# ESPLed.net
KiCad netlist of a schematic drawn in EAGLE
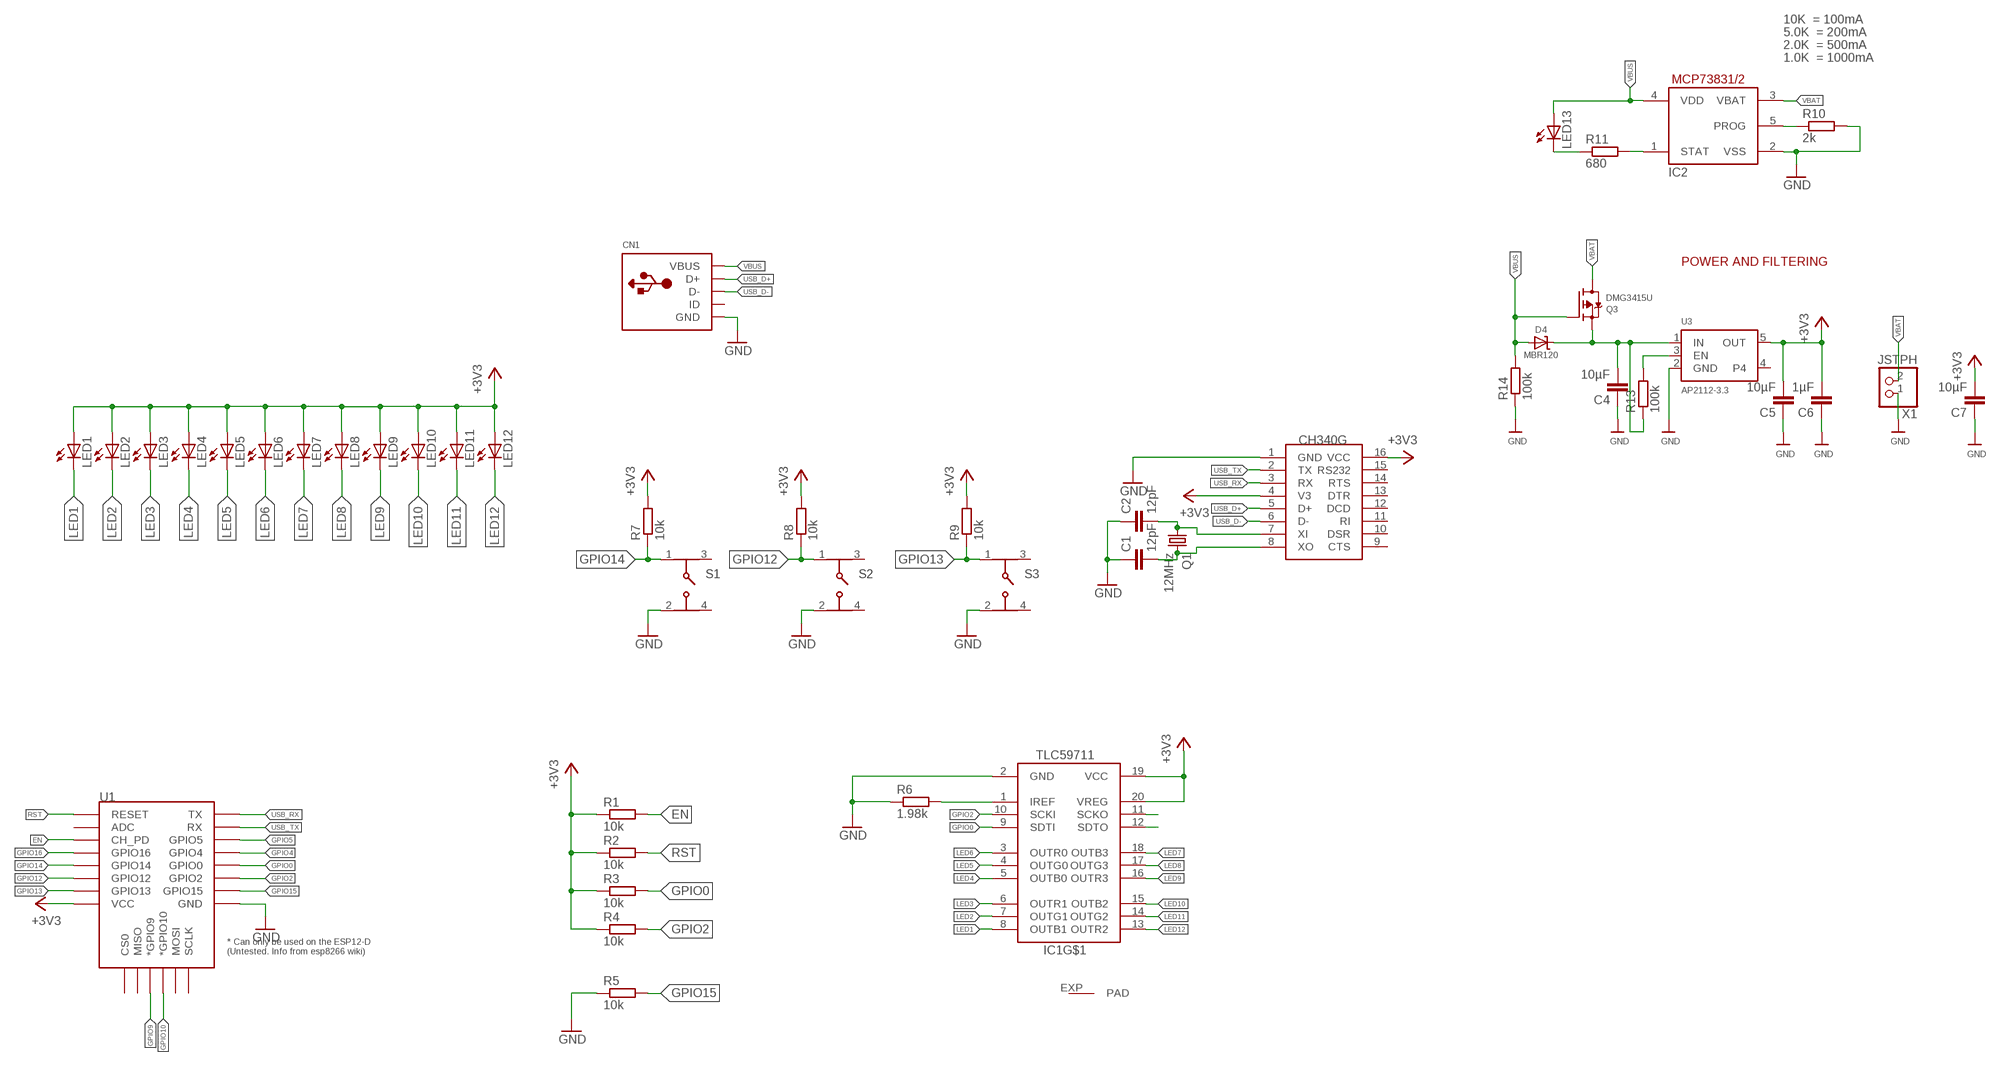
[diagram p0: schematic, sheet 1]

(export (version "E")
  (design (tool "Eeschema 10.0.6"))
  (components
    (comp (ref "C1")
      (value "12pF")
      (footprint "eagle-import:C0805")
      (libsource (lib "eagle-import") (part "C-EUC0805"))
    )
    (comp (ref "C2")
      (value "12pF")
      (footprint "eagle-import:C0805")
      (libsource (lib "eagle-import") (part "C-EUC0805"))
    )
    (comp (ref "C4")
      (value "10µF")
      (footprint "eagle-import:C0805")
      (libsource (lib "eagle-import") (part "C-EUC0805"))
    )
    (comp (ref "C5")
      (value "10µF")
      (footprint "eagle-import:C0805")
      (libsource (lib "eagle-import") (part "C-EUC0805"))
    )
    (comp (ref "C6")
      (value "1µF")
      (footprint "eagle-import:C0805")
      (libsource (lib "eagle-import") (part "C-EUC0805"))
    )
    (comp (ref "C7")
      (value "10µF")
      (footprint "eagle-import:C0805")
      (libsource (lib "eagle-import") (part "C-EUC0805"))
    )
    (comp (ref "CN1")
      (value "USBMINIB")
      (footprint "eagle-import:USB-MINIB")
      (libsource (lib "eagle-import") (part "USBMINIB"))
    )
    (comp (ref "D4")
      (value "MBR120")
      (footprint "eagle-import:SOD-123")
      (libsource (lib "eagle-import") (part "DIODE-SCHOTTKYSOD-123"))
    )
    (comp (ref "IC1")
      (value "TLC59711")
      (footprint "eagle-import:HTSSOP20DAP")
      (libsource (lib "eagle-import") (part "TLC59711"))
    )
    (comp (ref "IC2")
      (value "MCP73831/OT")
      (footprint "eagle-import:SOT23-5L")
      (libsource (lib "eagle-import") (part "MCP73831/OT"))
    )
    (comp (ref "LED1")
      (value "LEDSML0805")
      (footprint "eagle-import:SML0805")
      (libsource (lib "eagle-import") (part "LEDSML0805"))
    )
    (comp (ref "LED2")
      (value "LEDSML0805")
      (footprint "eagle-import:SML0805")
      (libsource (lib "eagle-import") (part "LEDSML0805"))
    )
    (comp (ref "LED3")
      (value "LEDSML0805")
      (footprint "eagle-import:SML0805")
      (libsource (lib "eagle-import") (part "LEDSML0805"))
    )
    (comp (ref "LED4")
      (value "LEDSML0805")
      (footprint "eagle-import:SML0805")
      (libsource (lib "eagle-import") (part "LEDSML0805"))
    )
    (comp (ref "LED5")
      (value "LEDSML0805")
      (footprint "eagle-import:SML0805")
      (libsource (lib "eagle-import") (part "LEDSML0805"))
    )
    (comp (ref "LED6")
      (value "LEDSML0805")
      (footprint "eagle-import:SML0805")
      (libsource (lib "eagle-import") (part "LEDSML0805"))
    )
    (comp (ref "LED7")
      (value "LEDSML0805")
      (footprint "eagle-import:SML0805")
      (libsource (lib "eagle-import") (part "LEDSML0805"))
    )
    (comp (ref "LED8")
      (value "LEDSML0805")
      (footprint "eagle-import:SML0805")
      (libsource (lib "eagle-import") (part "LEDSML0805"))
    )
    (comp (ref "LED9")
      (value "LEDSML0805")
      (footprint "eagle-import:SML0805")
      (libsource (lib "eagle-import") (part "LEDSML0805"))
    )
    (comp (ref "LED10")
      (value "LEDSML0805")
      (footprint "eagle-import:SML0805")
      (libsource (lib "eagle-import") (part "LEDSML0805"))
    )
    (comp (ref "LED11")
      (value "LEDSML0805")
      (footprint "eagle-import:SML0805")
      (libsource (lib "eagle-import") (part "LEDSML0805"))
    )
    (comp (ref "LED12")
      (value "LEDSML0805")
      (footprint "eagle-import:SML0805")
      (libsource (lib "eagle-import") (part "LEDSML0805"))
    )
    (comp (ref "LED13")
      (value "LEDSML0805")
      (footprint "eagle-import:SML0805")
      (libsource (lib "eagle-import") (part "LEDSML0805"))
    )
    (comp (ref "Q1")
      (value "12MHz")
      (footprint "eagle-import:CX5032GB")
      (libsource (lib "eagle-import") (part "CX5032GB12000H0PESZZ"))
    )
    (comp (ref "Q3")
      (value "DMG3415U")
      (footprint "eagle-import:SOT23-R")
      (libsource (lib "eagle-import") (part "MOSFET-P"))
    )
    (comp (ref "R1")
      (value "10k")
      (footprint "eagle-import:R0805")
      (libsource (lib "eagle-import") (part "R-EU_R0805"))
    )
    (comp (ref "R2")
      (value "10k")
      (footprint "eagle-import:R0805")
      (libsource (lib "eagle-import") (part "R-EU_R0805"))
    )
    (comp (ref "R3")
      (value "10k")
      (footprint "eagle-import:R0805")
      (libsource (lib "eagle-import") (part "R-EU_R0805"))
    )
    (comp (ref "R4")
      (value "10k")
      (footprint "eagle-import:R0805")
      (libsource (lib "eagle-import") (part "R-EU_R0805"))
    )
    (comp (ref "R5")
      (value "10k")
      (footprint "eagle-import:R0805")
      (libsource (lib "eagle-import") (part "R-EU_R0805"))
    )
    (comp (ref "R6")
      (value "1.98k")
      (footprint "eagle-import:R0805")
      (libsource (lib "eagle-import") (part "R-EU_R0805"))
    )
    (comp (ref "R7")
      (value "10k")
      (footprint "eagle-import:R0805")
      (libsource (lib "eagle-import") (part "R-EU_R0805"))
    )
    (comp (ref "R8")
      (value "10k")
      (footprint "eagle-import:R0805")
      (libsource (lib "eagle-import") (part "R-EU_R0805"))
    )
    (comp (ref "R9")
      (value "10k")
      (footprint "eagle-import:R0805")
      (libsource (lib "eagle-import") (part "R-EU_R0805"))
    )
    (comp (ref "R10")
      (value "2k")
      (footprint "eagle-import:R0805")
      (libsource (lib "eagle-import") (part "R-EU_R0805"))
    )
    (comp (ref "R11")
      (value "680")
      (footprint "eagle-import:R0805")
      (libsource (lib "eagle-import") (part "R-EU_R0805"))
    )
    (comp (ref "R13")
      (value "100k")
      (footprint "eagle-import:R0805")
      (libsource (lib "eagle-import") (part "R-EU_R0805"))
    )
    (comp (ref "R14")
      (value "100k")
      (footprint "eagle-import:R0805")
      (libsource (lib "eagle-import") (part "R-EU_R0805"))
    )
    (comp (ref "S1")
      (value "4301X6XXX7X6_430156043726")
      (footprint "eagle-import:4301X6XXX7X6")
      (libsource (lib "eagle-import") (part "4301X6XXX7X6_430156043726"))
    )
    (comp (ref "S2")
      (value "4301X6XXX7X6_430156043726")
      (footprint "eagle-import:4301X6XXX7X6")
      (libsource (lib "eagle-import") (part "4301X6XXX7X6_430156043726"))
    )
    (comp (ref "S3")
      (value "4301X6XXX7X6_430156043726")
      (footprint "eagle-import:4301X6XXX7X6")
      (libsource (lib "eagle-import") (part "4301X6XXX7X6_430156043726"))
    )
    (comp (ref "U$1")
      (value "CH340G")
      (footprint "eagle-import:SOIC16")
      (libsource (lib "eagle-import") (part "CH340G"))
    )
    (comp (ref "U1")
      (value "ESP12ESMD")
      (footprint "eagle-import:ESP12E-SMD")
      (libsource (lib "eagle-import") (part "ESP12ESMD"))
    )
    (comp (ref "U3")
      (value "AP2112-3.3")
      (footprint "eagle-import:SOT23-5")
      (libsource (lib "eagle-import") (part "VREG_SOT23-5"))
    )
    (comp (ref "X1")
      (value "JSTPH")
      (footprint "eagle-import:JSTPH2")
      (libsource (lib "eagle-import") (part "CON_JST_PH_2PIN"))
    )
  )
  (nets
    (net (code "1") (name "+3V3") (class "Default")
      (node (ref "C5") (pin "2") (pinfunction "2_2") (pintype "passive"))
      (node (ref "C6") (pin "2") (pinfunction "2_2") (pintype "passive"))
      (node (ref "C7") (pin "2") (pinfunction "2_2") (pintype "passive"))
      (node (ref "IC1") (pin "19") (pinfunction "VCC_19") (pintype "power_in"))
      (node (ref "IC1") (pin "20") (pinfunction "VREG_20") (pintype "bidirectional"))
      (node (ref "LED1") (pin "A") (pinfunction "A_A") (pintype "passive"))
      (node (ref "LED10") (pin "A") (pinfunction "A_A") (pintype "passive"))
      (node (ref "LED11") (pin "A") (pinfunction "A_A") (pintype "passive"))
      (node (ref "LED12") (pin "A") (pinfunction "A_A") (pintype "passive"))
      (node (ref "LED2") (pin "A") (pinfunction "A_A") (pintype "passive"))
      (node (ref "LED3") (pin "A") (pinfunction "A_A") (pintype "passive"))
      (node (ref "LED4") (pin "A") (pinfunction "A_A") (pintype "passive"))
      (node (ref "LED5") (pin "A") (pinfunction "A_A") (pintype "passive"))
      (node (ref "LED6") (pin "A") (pinfunction "A_A") (pintype "passive"))
      (node (ref "LED7") (pin "A") (pinfunction "A_A") (pintype "passive"))
      (node (ref "LED8") (pin "A") (pinfunction "A_A") (pintype "passive"))
      (node (ref "LED9") (pin "A") (pinfunction "A_A") (pintype "passive"))
      (node (ref "R1") (pin "1") (pinfunction "1_1") (pintype "passive"))
      (node (ref "R2") (pin "1") (pinfunction "1_1") (pintype "passive"))
      (node (ref "R3") (pin "1") (pinfunction "1_1") (pintype "passive"))
      (node (ref "R4") (pin "1") (pinfunction "1_1") (pintype "passive"))
      (node (ref "R7") (pin "2") (pinfunction "2_2") (pintype "passive"))
      (node (ref "R8") (pin "2") (pinfunction "2_2") (pintype "passive"))
      (node (ref "R9") (pin "2") (pinfunction "2_2") (pintype "passive"))
      (node (ref "U$1") (pin "16") (pinfunction "VCC_16") (pintype "bidirectional"))
      (node (ref "U$1") (pin "4") (pinfunction "V3_4") (pintype "bidirectional"))
      (node (ref "U1") (pin "VCC") (pinfunction "VCC_VCC") (pintype "bidirectional"))
      (node (ref "U3") (pin "5") (pinfunction "OUT_5") (pintype "power_in"))
    )
    (net (code "2") (name "EN") (class "Default")
      (node (ref "R1") (pin "2") (pinfunction "2_2") (pintype "passive"))
      (node (ref "U1") (pin "CH_PD") (pinfunction "CH_PD_CH_PD") (pintype "bidirectional"))
    )
    (net (code "3") (name "GND") (class "Default")
      (node (ref "C1") (pin "1") (pinfunction "1_1") (pintype "passive"))
      (node (ref "C2") (pin "1") (pinfunction "1_1") (pintype "passive"))
      (node (ref "C4") (pin "1") (pinfunction "1_1") (pintype "passive"))
      (node (ref "C5") (pin "1") (pinfunction "1_1") (pintype "passive"))
      (node (ref "C6") (pin "1") (pinfunction "1_1") (pintype "passive"))
      (node (ref "C7") (pin "1") (pinfunction "1_1") (pintype "passive"))
      (node (ref "CN1") (pin "GND") (pinfunction "GND_GND") (pintype "power_in"))
      (node (ref "IC1") (pin "2") (pinfunction "GND_2") (pintype "power_in"))
      (node (ref "IC2") (pin "2") (pinfunction "VSS_2") (pintype "power_in"))
      (node (ref "R10") (pin "2") (pinfunction "2_2") (pintype "passive"))
      (node (ref "R14") (pin "1") (pinfunction "1_1") (pintype "passive"))
      (node (ref "R5") (pin "1") (pinfunction "1_1") (pintype "passive"))
      (node (ref "R6") (pin "1") (pinfunction "1_1") (pintype "passive"))
      (node (ref "S1") (pin "2") (pinfunction "2_2") (pintype "passive"))
      (node (ref "S2") (pin "2") (pinfunction "2_2") (pintype "passive"))
      (node (ref "S3") (pin "2") (pinfunction "2_2") (pintype "passive"))
      (node (ref "U$1") (pin "1") (pinfunction "GND_1") (pintype "bidirectional"))
      (node (ref "U1") (pin "GND") (pinfunction "GND_GND") (pintype "bidirectional"))
      (node (ref "U3") (pin "2") (pinfunction "GND_2") (pintype "power_in"))
      (node (ref "X1") (pin "1") (pinfunction "1_1") (pintype "passive"))
    )
    (net (code "4") (name "GPIO0") (class "Default")
      (node (ref "IC1") (pin "9") (pinfunction "SDTI_9") (pintype "input"))
      (node (ref "R3") (pin "2") (pinfunction "2_2") (pintype "passive"))
      (node (ref "U1") (pin "GPIO0") (pinfunction "GPIO0_GPIO0") (pintype "bidirectional"))
    )
    (net (code "5") (name "GPIO2") (class "Default")
      (node (ref "IC1") (pin "10") (pinfunction "SCKI_10") (pintype "input"))
      (node (ref "R4") (pin "2") (pinfunction "2_2") (pintype "passive"))
      (node (ref "U1") (pin "GPIO2") (pinfunction "GPIO2_GPIO2") (pintype "bidirectional"))
    )
    (net (code "6") (name "GPIO4") (class "Default")
      (node (ref "U1") (pin "GPIO4") (pinfunction "GPIO4_GPIO4") (pintype "bidirectional"))
    )
    (net (code "7") (name "GPIO5") (class "Default")
      (node (ref "U1") (pin "GPIO5") (pinfunction "GPIO5_GPIO5") (pintype "bidirectional"))
    )
    (net (code "8") (name "GPIO9") (class "Default")
      (node (ref "U1") (pin "GPIO9") (pinfunction "*GPIO9_GPIO9") (pintype "bidirectional"))
    )
    (net (code "9") (name "GPIO10") (class "Default")
      (node (ref "U1") (pin "GPIO10") (pinfunction "*GPIO10_GPIO10") (pintype "bidirectional"))
    )
    (net (code "10") (name "GPIO12") (class "Default")
      (node (ref "R8") (pin "1") (pinfunction "1_1") (pintype "passive"))
      (node (ref "S2") (pin "1") (pinfunction "1_1") (pintype "passive"))
      (node (ref "U1") (pin "GPIO12") (pinfunction "GPIO12_GPIO12") (pintype "bidirectional"))
    )
    (net (code "11") (name "GPIO13") (class "Default")
      (node (ref "R9") (pin "1") (pinfunction "1_1") (pintype "passive"))
      (node (ref "S3") (pin "1") (pinfunction "1_1") (pintype "passive"))
      (node (ref "U1") (pin "GPIO13") (pinfunction "GPIO13_GPIO13") (pintype "bidirectional"))
    )
    (net (code "12") (name "GPIO14") (class "Default")
      (node (ref "R7") (pin "1") (pinfunction "1_1") (pintype "passive"))
      (node (ref "S1") (pin "1") (pinfunction "1_1") (pintype "passive"))
      (node (ref "U1") (pin "GPIO14") (pinfunction "GPIO14_GPIO14") (pintype "bidirectional"))
    )
    (net (code "13") (name "GPIO15") (class "Default")
      (node (ref "R5") (pin "2") (pinfunction "2_2") (pintype "passive"))
      (node (ref "U1") (pin "GPIO15") (pinfunction "GPIO15_GPIO15") (pintype "bidirectional"))
    )
    (net (code "14") (name "GPIO16") (class "Default")
      (node (ref "U1") (pin "GPIO16") (pinfunction "GPIO16_GPIO16") (pintype "bidirectional"))
    )
    (net (code "15") (name "LED1") (class "Default")
      (node (ref "IC1") (pin "8") (pinfunction "OUTB1_8") (pintype "open_collector"))
      (node (ref "LED1") (pin "C") (pinfunction "C_C") (pintype "passive"))
    )
    (net (code "16") (name "LED2") (class "Default")
      (node (ref "IC1") (pin "7") (pinfunction "OUTG1_7") (pintype "open_collector"))
      (node (ref "LED2") (pin "C") (pinfunction "C_C") (pintype "passive"))
    )
    (net (code "17") (name "LED3") (class "Default")
      (node (ref "IC1") (pin "6") (pinfunction "OUTR1_6") (pintype "open_collector"))
      (node (ref "LED3") (pin "C") (pinfunction "C_C") (pintype "passive"))
    )
    (net (code "18") (name "LED4") (class "Default")
      (node (ref "IC1") (pin "5") (pinfunction "OUTB0_5") (pintype "open_collector"))
      (node (ref "LED4") (pin "C") (pinfunction "C_C") (pintype "passive"))
    )
    (net (code "19") (name "LED5") (class "Default")
      (node (ref "IC1") (pin "4") (pinfunction "OUTG0_4") (pintype "open_collector"))
      (node (ref "LED5") (pin "C") (pinfunction "C_C") (pintype "passive"))
    )
    (net (code "20") (name "LED6") (class "Default")
      (node (ref "IC1") (pin "3") (pinfunction "OUTR0_3") (pintype "open_collector"))
      (node (ref "LED6") (pin "C") (pinfunction "C_C") (pintype "passive"))
    )
    (net (code "21") (name "LED7") (class "Default")
      (node (ref "IC1") (pin "18") (pinfunction "OUTB3_18") (pintype "open_collector"))
      (node (ref "LED7") (pin "C") (pinfunction "C_C") (pintype "passive"))
    )
    (net (code "22") (name "LED8") (class "Default")
      (node (ref "IC1") (pin "17") (pinfunction "OUTG3_17") (pintype "open_collector"))
      (node (ref "LED8") (pin "C") (pinfunction "C_C") (pintype "passive"))
    )
    (net (code "23") (name "LED9") (class "Default")
      (node (ref "IC1") (pin "16") (pinfunction "OUTR3_16") (pintype "open_collector"))
      (node (ref "LED9") (pin "C") (pinfunction "C_C") (pintype "passive"))
    )
    (net (code "24") (name "LED10") (class "Default")
      (node (ref "IC1") (pin "15") (pinfunction "OUTB2_15") (pintype "open_collector"))
      (node (ref "LED10") (pin "C") (pinfunction "C_C") (pintype "passive"))
    )
    (net (code "25") (name "LED11") (class "Default")
      (node (ref "IC1") (pin "14") (pinfunction "OUTG2_14") (pintype "open_collector"))
      (node (ref "LED11") (pin "C") (pinfunction "C_C") (pintype "passive"))
    )
    (net (code "26") (name "LED12") (class "Default")
      (node (ref "IC1") (pin "13") (pinfunction "OUTR2_13") (pintype "open_collector"))
      (node (ref "LED12") (pin "C") (pinfunction "C_C") (pintype "passive"))
    )
    (net (code "27") (name "Net-(IC1A-IREF)") (class "Default")
      (node (ref "IC1") (pin "1") (pinfunction "IREF_1") (pintype "bidirectional"))
      (node (ref "R6") (pin "2") (pinfunction "2_2") (pintype "passive"))
    )
    (net (code "28") (name "Net-(IC2-PROG)") (class "Default")
      (node (ref "IC2") (pin "5") (pinfunction "PROG_5") (pintype "input"))
      (node (ref "R10") (pin "1") (pinfunction "1_1") (pintype "passive"))
    )
    (net (code "29") (name "Net-(IC2-STAT)") (class "Default")
      (node (ref "IC2") (pin "1") (pinfunction "STAT_1") (pintype "output"))
      (node (ref "R11") (pin "2") (pinfunction "2_2") (pintype "passive"))
    )
    (net (code "30") (name "Net-(LED13-PadC)") (class "Default")
      (node (ref "LED13") (pin "C") (pinfunction "C_C") (pintype "passive"))
      (node (ref "R11") (pin "1") (pinfunction "1_1") (pintype "passive"))
    )
    (net (code "31") (name "Net-(Q1-1)") (class "Default")
      (node (ref "C2") (pin "2") (pinfunction "2_2") (pintype "passive"))
      (node (ref "Q1") (pin "P$1") (pinfunction "1_P$1") (pintype "passive"))
      (node (ref "U$1") (pin "7") (pinfunction "XI_7") (pintype "bidirectional"))
    )
    (net (code "32") (name "Net-(Q1-2)") (class "Default")
      (node (ref "C1") (pin "2") (pinfunction "2_2") (pintype "passive"))
      (node (ref "Q1") (pin "P$2") (pinfunction "2_P$2") (pintype "passive"))
      (node (ref "U$1") (pin "8") (pinfunction "XO_8") (pintype "bidirectional"))
    )
    (net (code "33") (name "Net-(Q3-S)") (class "Default")
      (node (ref "C4") (pin "2") (pinfunction "2_2") (pintype "passive"))
      (node (ref "D4") (pin "C") (pinfunction "C_C") (pintype "passive"))
      (node (ref "Q3") (pin "2") (pinfunction "S_2") (pintype "passive"))
      (node (ref "R13") (pin "1") (pinfunction "1_1") (pintype "passive"))
      (node (ref "U3") (pin "1") (pinfunction "IN_1") (pintype "power_in"))
    )
    (net (code "34") (name "Net-(U3-EN)") (class "Default")
      (node (ref "R13") (pin "2") (pinfunction "2_2") (pintype "passive"))
      (node (ref "U3") (pin "3") (pinfunction "EN_3") (pintype "input"))
    )
    (net (code "35") (name "RST") (class "Default")
      (node (ref "R2") (pin "2") (pinfunction "2_2") (pintype "passive"))
      (node (ref "U1") (pin "RESET") (pinfunction "RESET_RESET") (pintype "bidirectional"))
    )
    (net (code "36") (name "USB_D+") (class "Default")
      (node (ref "CN1") (pin "D+") (pinfunction "D+_D+") (pintype "bidirectional"))
      (node (ref "U$1") (pin "5") (pinfunction "D+_5") (pintype "bidirectional"))
    )
    (net (code "37") (name "USB_D-") (class "Default")
      (node (ref "CN1") (pin "D-") (pinfunction "D-_D-") (pintype "bidirectional"))
      (node (ref "U$1") (pin "6") (pinfunction "D-_6") (pintype "bidirectional"))
    )
    (net (code "38") (name "USB_RX") (class "Default")
      (node (ref "U$1") (pin "3") (pinfunction "RX_3") (pintype "bidirectional"))
      (node (ref "U1") (pin "TXD0") (pinfunction "TX_TXD0") (pintype "bidirectional"))
    )
    (net (code "39") (name "USB_TX") (class "Default")
      (node (ref "U$1") (pin "2") (pinfunction "TX_2") (pintype "bidirectional"))
      (node (ref "U1") (pin "RXD0") (pinfunction "RX_RXD0") (pintype "bidirectional"))
    )
    (net (code "40") (name "VBAT") (class "Default")
      (node (ref "IC2") (pin "3") (pinfunction "VBAT_3") (pintype "bidirectional"))
      (node (ref "Q3") (pin "3") (pinfunction "D_3") (pintype "passive"))
      (node (ref "X1") (pin "2") (pinfunction "2_2") (pintype "passive"))
    )
    (net (code "41") (name "VBUS") (class "Default")
      (node (ref "CN1") (pin "VBUS") (pinfunction "VBUS_VBUS") (pintype "power_in"))
      (node (ref "D4") (pin "A") (pinfunction "A_A") (pintype "passive"))
      (node (ref "IC2") (pin "4") (pinfunction "VDD_4") (pintype "power_in"))
      (node (ref "LED13") (pin "A") (pinfunction "A_A") (pintype "passive"))
      (node (ref "Q3") (pin "1") (pinfunction "G_1") (pintype "passive"))
      (node (ref "R14") (pin "2") (pinfunction "2_2") (pintype "passive"))
    )
    (net (code "42") (name "unconnected-(CN1-PadID)") (class "Default")
      (node (ref "CN1") (pin "ID") (pinfunction "ID_ID") (pintype "bidirectional"))
    )
    (net (code "43") (name "unconnected-(IC1A-SCKO-Pad11)") (class "Default")
      (node (ref "IC1") (pin "11") (pinfunction "SCKO_11") (pintype "output"))
    )
    (net (code "44") (name "unconnected-(IC1A-SDTO-Pad12)") (class "Default")
      (node (ref "IC1") (pin "12") (pinfunction "SDTO_12") (pintype "output"))
    )
    (net (code "45") (name "unconnected-(IC1B-PAD-PadEXP)") (class "Default")
      (node (ref "IC1") (pin "EXP") (pinfunction "PAD_EXP") (pintype "passive"))
    )
    (net (code "46") (name "unconnected-(S1-Pad3)") (class "Default")
      (node (ref "S1") (pin "3") (pinfunction "3_3") (pintype "passive"))
    )
    (net (code "47") (name "unconnected-(S1-Pad4)") (class "Default")
      (node (ref "S1") (pin "4") (pinfunction "4_4") (pintype "passive"))
    )
    (net (code "48") (name "unconnected-(S2-Pad3)") (class "Default")
      (node (ref "S2") (pin "3") (pinfunction "3_3") (pintype "passive"))
    )
    (net (code "49") (name "unconnected-(S2-Pad4)") (class "Default")
      (node (ref "S2") (pin "4") (pinfunction "4_4") (pintype "passive"))
    )
    (net (code "50") (name "unconnected-(S3-Pad3)") (class "Default")
      (node (ref "S3") (pin "3") (pinfunction "3_3") (pintype "passive"))
    )
    (net (code "51") (name "unconnected-(S3-Pad4)") (class "Default")
      (node (ref "S3") (pin "4") (pinfunction "4_4") (pintype "passive"))
    )
    (net (code "52") (name "unconnected-(U$1-CTS-Pad9)") (class "Default")
      (node (ref "U$1") (pin "9") (pinfunction "CTS_9") (pintype "bidirectional"))
    )
    (net (code "53") (name "unconnected-(U$1-DCD-Pad12)") (class "Default")
      (node (ref "U$1") (pin "12") (pinfunction "DCD_12") (pintype "bidirectional"))
    )
    (net (code "54") (name "unconnected-(U$1-DSR-Pad10)") (class "Default")
      (node (ref "U$1") (pin "10") (pinfunction "DSR_10") (pintype "bidirectional"))
    )
    (net (code "55") (name "unconnected-(U$1-DTR-Pad13)") (class "Default")
      (node (ref "U$1") (pin "13") (pinfunction "DTR_13") (pintype "bidirectional"))
    )
    (net (code "56") (name "unconnected-(U$1-RI-Pad11)") (class "Default")
      (node (ref "U$1") (pin "11") (pinfunction "RI_11") (pintype "bidirectional"))
    )
    (net (code "57") (name "unconnected-(U$1-RS232-Pad15)") (class "Default")
      (node (ref "U$1") (pin "15") (pinfunction "RS232_15") (pintype "bidirectional"))
    )
    (net (code "58") (name "unconnected-(U$1-RTS-Pad14)") (class "Default")
      (node (ref "U$1") (pin "14") (pinfunction "RTS_14") (pintype "bidirectional"))
    )
    (net (code "59") (name "unconnected-(U1-PadADC)") (class "Default")
      (node (ref "U1") (pin "ADC") (pinfunction "ADC_ADC") (pintype "bidirectional"))
    )
    (net (code "60") (name "unconnected-(U1-PadCS0)") (class "Default")
      (node (ref "U1") (pin "CS0") (pinfunction "CS0_CS0") (pintype "bidirectional"))
    )
    (net (code "61") (name "unconnected-(U1-PadMISO)") (class "Default")
      (node (ref "U1") (pin "MISO") (pinfunction "MISO_MISO") (pintype "bidirectional"))
    )
    (net (code "62") (name "unconnected-(U1-PadMOSI)") (class "Default")
      (node (ref "U1") (pin "MOSI") (pinfunction "MOSI_MOSI") (pintype "bidirectional"))
    )
    (net (code "63") (name "unconnected-(U1-PadSCLK)") (class "Default")
      (node (ref "U1") (pin "SCLK") (pinfunction "SCLK_SCLK") (pintype "bidirectional"))
    )
    (net (code "64") (name "unconnected-(U3-P4-Pad4)") (class "Default")
      (node (ref "U3") (pin "4") (pinfunction "P4_4") (pintype "bidirectional"))
    )
  )
)
